# digital_led_panel.net
KiCad netlist of a schematic drawn in Altium Designer
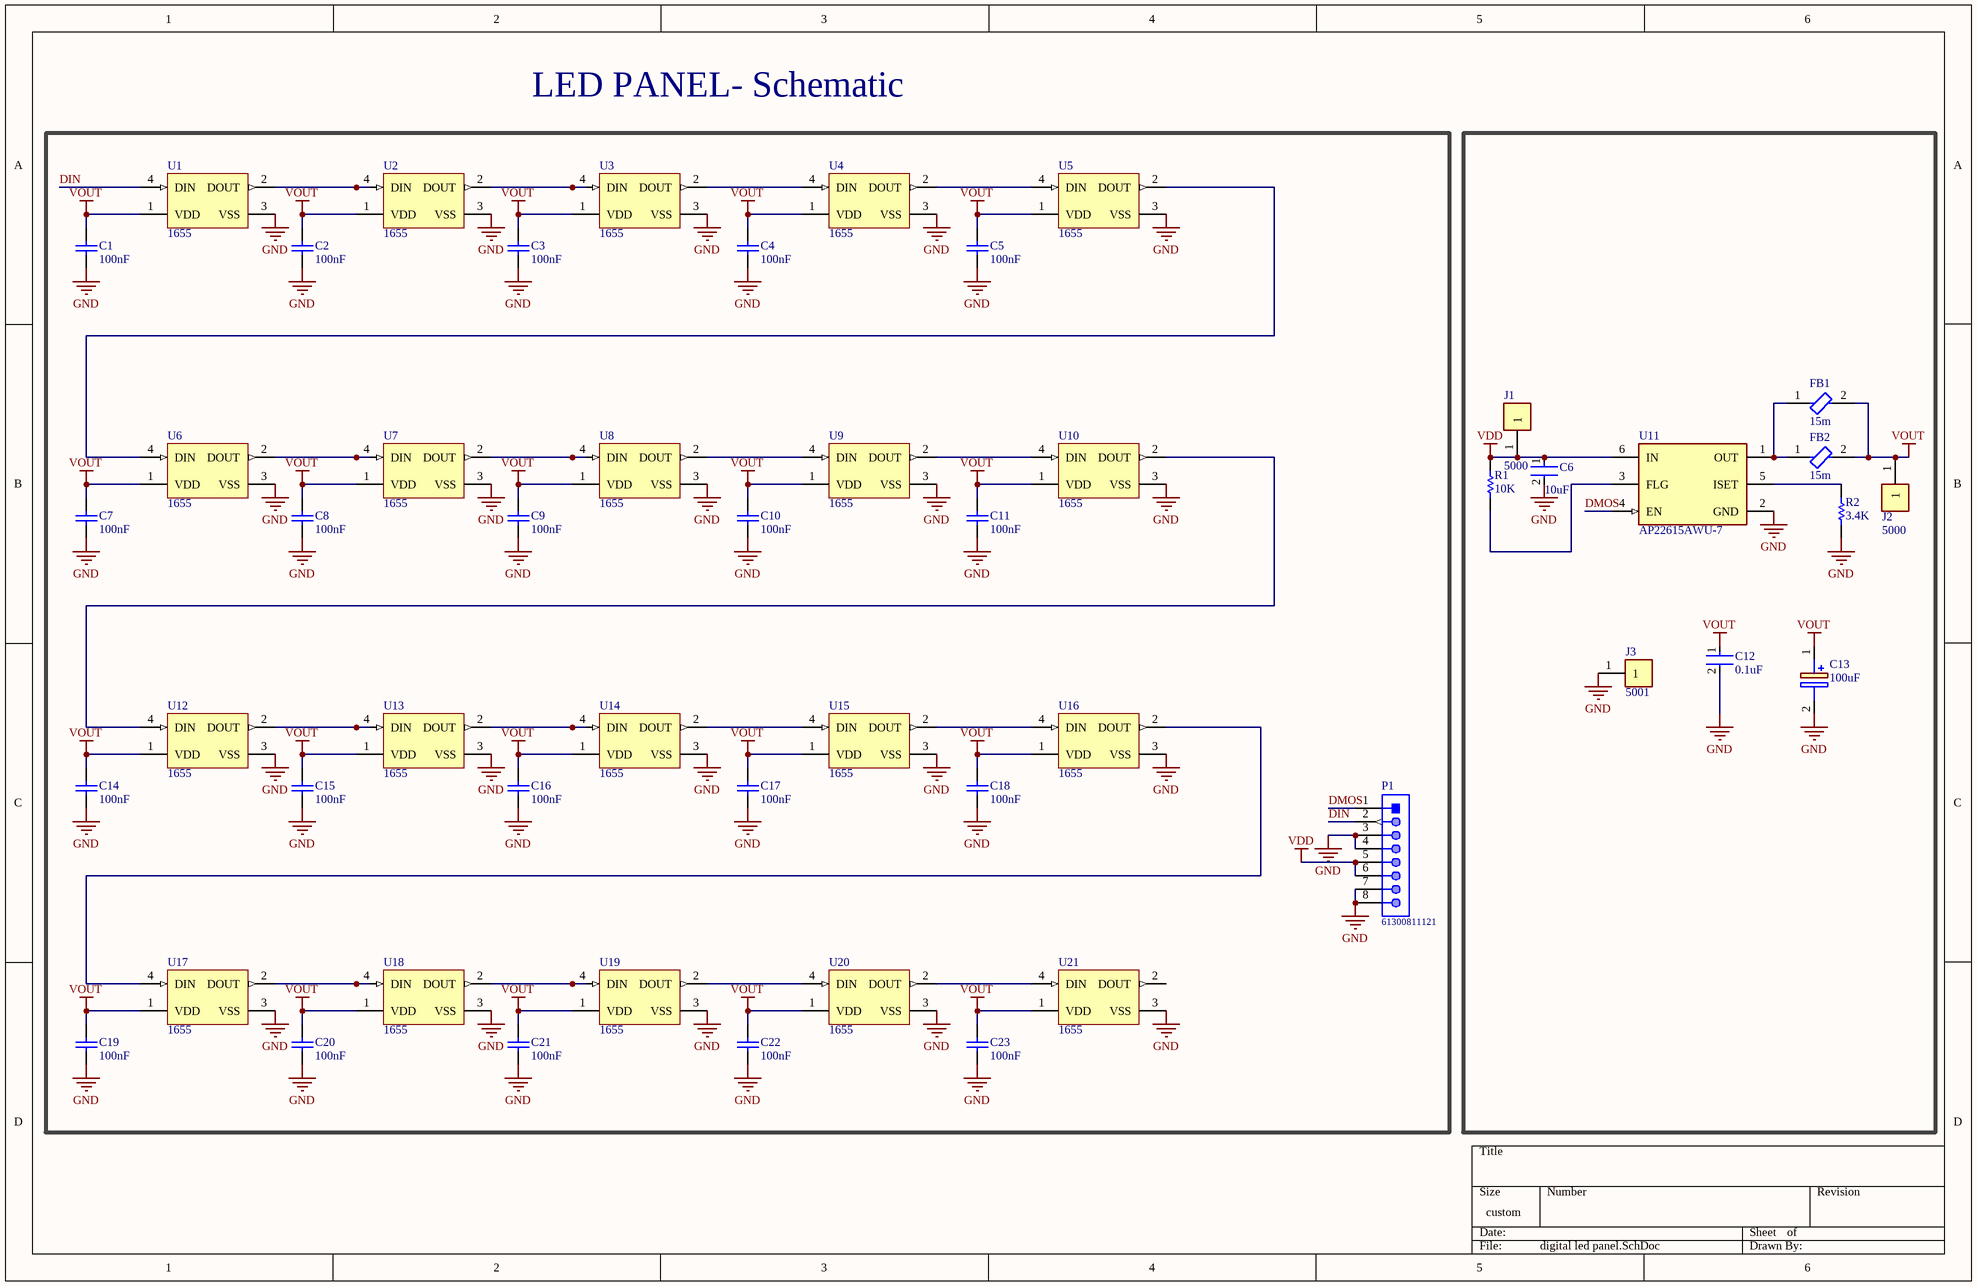
[diagram p0: digital led panel.SchDoc]

(export (version "E")
  (design (tool "Eeschema 10.0.6"))
  (components
    (comp (ref "C1")
      (value "100nF")
      (footprint "KEMT-1206-2_M")
      (description "CAP, Ceramic, 0.1 uF, +/- 10%, 50 V, -55 to 125 degC, 1206 (3216 Metric), RoHS, Tape and Reel")
      (fields (field (name "MANUFACTURER") "Kemet"))
      (libsource (lib "Altium Content Vault") (part "CAP-NP-2"))
    )
    (comp (ref "C2")
      (value "100nF")
      (footprint "KEMT-1206-2_M")
      (description "CAP, Ceramic, 0.1 uF, +/- 10%, 50 V, -55 to 125 degC, 1206 (3216 Metric), RoHS, Tape and Reel")
      (fields (field (name "MANUFACTURER") "Kemet"))
      (libsource (lib "Altium Content Vault") (part "CAP-NP-2"))
    )
    (comp (ref "C3")
      (value "100nF")
      (footprint "KEMT-1206-2_M")
      (description "CAP, Ceramic, 0.1 uF, +/- 10%, 50 V, -55 to 125 degC, 1206 (3216 Metric), RoHS, Tape and Reel")
      (fields (field (name "MANUFACTURER") "Kemet"))
      (libsource (lib "Altium Content Vault") (part "CAP-NP-2"))
    )
    (comp (ref "C4")
      (value "100nF")
      (footprint "KEMT-1206-2_M")
      (description "CAP, Ceramic, 0.1 uF, +/- 10%, 50 V, -55 to 125 degC, 1206 (3216 Metric), RoHS, Tape and Reel")
      (fields (field (name "MANUFACTURER") "Kemet"))
      (libsource (lib "Altium Content Vault") (part "CAP-NP-2"))
    )
    (comp (ref "C5")
      (value "100nF")
      (footprint "KEMT-1206-2_M")
      (description "CAP, Ceramic, 0.1 uF, +/- 10%, 50 V, -55 to 125 degC, 1206 (3216 Metric), RoHS, Tape and Reel")
      (fields (field (name "MANUFACTURER") "Kemet"))
      (libsource (lib "Altium Content Vault") (part "CAP-NP-2"))
    )
    (comp (ref "C6")
      (value "10uF")
      (footprint "FP-1206-L_3_2_0_2-W_1_6_0-IPC_A")
      (description "General Purpose Ceramic Capacitor, 1206, 10uF, 10%, X5R, 15%, 10V")
      (fields (field (name "TOLERANCE") "10%") (field (name "VOLTAGE") "10V"))
      (libsource (lib "Altium Content Vault") (part "02cd4be3c70576c341d710602a673aa"))
    )
    (comp (ref "C7")
      (value "100nF")
      (footprint "KEMT-1206-2_M")
      (description "CAP, Ceramic, 0.1 uF, +/- 10%, 50 V, -55 to 125 degC, 1206 (3216 Metric), RoHS, Tape and Reel")
      (fields (field (name "MANUFACTURER") "Kemet"))
      (libsource (lib "Altium Content Vault") (part "CAP-NP-2"))
    )
    (comp (ref "C8")
      (value "100nF")
      (footprint "KEMT-1206-2_M")
      (description "CAP, Ceramic, 0.1 uF, +/- 10%, 50 V, -55 to 125 degC, 1206 (3216 Metric), RoHS, Tape and Reel")
      (fields (field (name "MANUFACTURER") "Kemet"))
      (libsource (lib "Altium Content Vault") (part "CAP-NP-2"))
    )
    (comp (ref "C9")
      (value "100nF")
      (footprint "KEMT-1206-2_M")
      (description "CAP, Ceramic, 0.1 uF, +/- 10%, 50 V, -55 to 125 degC, 1206 (3216 Metric), RoHS, Tape and Reel")
      (fields (field (name "MANUFACTURER") "Kemet"))
      (libsource (lib "Altium Content Vault") (part "CAP-NP-2"))
    )
    (comp (ref "C10")
      (value "100nF")
      (footprint "KEMT-1206-2_M")
      (description "CAP, Ceramic, 0.1 uF, +/- 10%, 50 V, -55 to 125 degC, 1206 (3216 Metric), RoHS, Tape and Reel")
      (fields (field (name "MANUFACTURER") "Kemet"))
      (libsource (lib "Altium Content Vault") (part "CAP-NP-2"))
    )
    (comp (ref "C11")
      (value "100nF")
      (footprint "KEMT-1206-2_M")
      (description "CAP, Ceramic, 0.1 uF, +/- 10%, 50 V, -55 to 125 degC, 1206 (3216 Metric), RoHS, Tape and Reel")
      (fields (field (name "MANUFACTURER") "Kemet"))
      (libsource (lib "Altium Content Vault") (part "CAP-NP-2"))
    )
    (comp (ref "C12")
      (value "0.1uF")
      (footprint "FP-C1206C-EB-MFG")
      (description "CAP CER 0.1UF 100V X7R 1206")
      (fields
        (field (name "TOLERANCE") "0.1")
        (field (name "OCTOPART") "https://octopart.com/c1206c104k1ractu-kemet-89521")
      )
      (libsource (lib "Altium Content Vault") (part "b4654b650e69147ec39a6b967a45e02"))
    )
    (comp (ref "C13")
      (value "100uF")
      (footprint "SamacSys:CAPAE660X565N")
      (description "Capacitor Polarised")
      (fields
        (field (name "MANUFACTURER_PART_NUMBER") "EEV107M016S9GAA")
        (field (name "MOUSER PART NUMBER") "80-EEV107M016S9GAA")
      )
      (libsource (lib "*") (part "EEV107M016S9GAA"))
    )
    (comp (ref "C14")
      (value "100nF")
      (footprint "KEMT-1206-2_M")
      (description "CAP, Ceramic, 0.1 uF, +/- 10%, 50 V, -55 to 125 degC, 1206 (3216 Metric), RoHS, Tape and Reel")
      (fields (field (name "MANUFACTURER") "Kemet"))
      (libsource (lib "Altium Content Vault") (part "CAP-NP-2"))
    )
    (comp (ref "C15")
      (value "100nF")
      (footprint "KEMT-1206-2_M")
      (description "CAP, Ceramic, 0.1 uF, +/- 10%, 50 V, -55 to 125 degC, 1206 (3216 Metric), RoHS, Tape and Reel")
      (fields (field (name "MANUFACTURER") "Kemet"))
      (libsource (lib "Altium Content Vault") (part "CAP-NP-2"))
    )
    (comp (ref "C16")
      (value "100nF")
      (footprint "KEMT-1206-2_M")
      (description "CAP, Ceramic, 0.1 uF, +/- 10%, 50 V, -55 to 125 degC, 1206 (3216 Metric), RoHS, Tape and Reel")
      (fields (field (name "MANUFACTURER") "Kemet"))
      (libsource (lib "Altium Content Vault") (part "CAP-NP-2"))
    )
    (comp (ref "C17")
      (value "100nF")
      (footprint "KEMT-1206-2_M")
      (description "CAP, Ceramic, 0.1 uF, +/- 10%, 50 V, -55 to 125 degC, 1206 (3216 Metric), RoHS, Tape and Reel")
      (fields (field (name "MANUFACTURER") "Kemet"))
      (libsource (lib "Altium Content Vault") (part "CAP-NP-2"))
    )
    (comp (ref "C18")
      (value "100nF")
      (footprint "KEMT-1206-2_M")
      (description "CAP, Ceramic, 0.1 uF, +/- 10%, 50 V, -55 to 125 degC, 1206 (3216 Metric), RoHS, Tape and Reel")
      (fields (field (name "MANUFACTURER") "Kemet"))
      (libsource (lib "Altium Content Vault") (part "CAP-NP-2"))
    )
    (comp (ref "C19")
      (value "100nF")
      (footprint "KEMT-1206-2_M")
      (description "CAP, Ceramic, 0.1 uF, +/- 10%, 50 V, -55 to 125 degC, 1206 (3216 Metric), RoHS, Tape and Reel")
      (fields (field (name "MANUFACTURER") "Kemet"))
      (libsource (lib "Altium Content Vault") (part "CAP-NP-2"))
    )
    (comp (ref "C20")
      (value "100nF")
      (footprint "KEMT-1206-2_M")
      (description "CAP, Ceramic, 0.1 uF, +/- 10%, 50 V, -55 to 125 degC, 1206 (3216 Metric), RoHS, Tape and Reel")
      (fields (field (name "MANUFACTURER") "Kemet"))
      (libsource (lib "Altium Content Vault") (part "CAP-NP-2"))
    )
    (comp (ref "C21")
      (value "100nF")
      (footprint "KEMT-1206-2_M")
      (description "CAP, Ceramic, 0.1 uF, +/- 10%, 50 V, -55 to 125 degC, 1206 (3216 Metric), RoHS, Tape and Reel")
      (fields (field (name "MANUFACTURER") "Kemet"))
      (libsource (lib "Altium Content Vault") (part "CAP-NP-2"))
    )
    (comp (ref "C22")
      (value "100nF")
      (footprint "KEMT-1206-2_M")
      (description "CAP, Ceramic, 0.1 uF, +/- 10%, 50 V, -55 to 125 degC, 1206 (3216 Metric), RoHS, Tape and Reel")
      (fields (field (name "MANUFACTURER") "Kemet"))
      (libsource (lib "Altium Content Vault") (part "CAP-NP-2"))
    )
    (comp (ref "C23")
      (value "100nF")
      (footprint "KEMT-1206-2_M")
      (description "CAP, Ceramic, 0.1 uF, +/- 10%, 50 V, -55 to 125 degC, 1206 (3216 Metric), RoHS, Tape and Reel")
      (fields (field (name "MANUFACTURER") "Kemet"))
      (libsource (lib "Altium Content Vault") (part "CAP-NP-2"))
    )
    (comp (ref "FB1")
      (value "15m")
      (footprint "FP-BLM21-0_2-t0_85-e0_5-d-IPC_B")
      (description "Chip Ferrite Bead, 0805, 30Ω @ 100MHz, 0.014Ω, , 4A")
      (fields (field (name "TOLERANCE") "25%"))
      (libsource (lib "Altium Content Vault") (part "5f30dd21d616792df468990f7003faa"))
    )
    (comp (ref "FB2")
      (value "15m")
      (footprint "FP-BLM21-0_2-t0_85-e0_5-d-IPC_B")
      (description "Chip Ferrite Bead, 0805, 30Ω @ 100MHz, 0.014Ω, , 4A")
      (fields (field (name "TOLERANCE") "25%"))
      (libsource (lib "Altium Content Vault") (part "5f30dd21d616792df468990f7003faa"))
    )
    (comp (ref "J1")
      (value "5000")
      (footprint "FP-5000-MFG")
      (description "PC TEST POINT MINIATURE RED")
      (libsource (lib "Altium Content Vault") (part "1e4615820a309e3ce90f9e6d957b7fa"))
    )
    (comp (ref "J2")
      (value "5000")
      (footprint "FP-5000-MFG")
      (description "PC TEST POINT MINIATURE RED")
      (libsource (lib "") (part "1e4615820a309e3ce90f9e6d957b7fa_2"))
    )
    (comp (ref "J3")
      (value "5001")
      (footprint "FP-5001-MFG")
      (description "PC TEST POINT MINIATURE BLACK")
      (libsource (lib "") (part "1e4615820a309e3ce90f9e6d957b7fa_1"))
    )
    (comp (ref "P1")
      (value "61300811121")
      (footprint "61300811121")
      (description "THT Vertical Pin Header WR-PHD, Pitch 2.54 mm, Single Row, 8 pins")
      (fields (field (name "MANUFACTURER") "Wurth Elektronik") (field (name "PUBLISHER") "WurthElektronik"))
      (libsource (lib "Altium Content Vault") (part "WE-CN-1P-M-R8"))
    )
    (comp (ref "R1")
      (value "10K")
      (footprint "RESC3116X65X40ML10T20")
      (description "Chip Resistor, 10 KOhm, +/- 1%, 0.25 W, -55 to 155 degC, 1206 (3216 Metric), RoHS, Tape and Reel")
      (fields (field (name "TOLERANCE") "1%") (field (name "MANUFACTURER") "Yageo"))
      (libsource (lib "Altium Content Vault") (part "RES-2"))
    )
    (comp (ref "R2")
      (value "3.4K")
      (footprint "RESC3216X70X50LL05T20")
      (fields (field (name "PART NUMBER") "ERJ-8ENF3401V") (field (name "MANUFACTURER") "Panasonic"))
      (libsource (lib "Altium Content Vault") (part "RES"))
    )
    (comp (ref "U1")
      (value "1655")
      (footprint "ADA-RGB-1655_V")
      (fields (field (name "MANUFACTURER") "Adafruit-Industries-LLC"))
      (libsource (lib "Altium Content Vault") (part "ADA-RGB-1655-4"))
    )
    (comp (ref "U2")
      (value "1655")
      (footprint "ADA-RGB-1655_V")
      (fields (field (name "MANUFACTURER") "Adafruit-Industries-LLC"))
      (libsource (lib "Altium Content Vault") (part "ADA-RGB-1655-4"))
    )
    (comp (ref "U3")
      (value "1655")
      (footprint "ADA-RGB-1655_V")
      (fields (field (name "MANUFACTURER") "Adafruit-Industries-LLC"))
      (libsource (lib "Altium Content Vault") (part "ADA-RGB-1655-4"))
    )
    (comp (ref "U4")
      (value "1655")
      (footprint "ADA-RGB-1655_V")
      (fields (field (name "MANUFACTURER") "Adafruit-Industries-LLC"))
      (libsource (lib "Altium Content Vault") (part "ADA-RGB-1655-4"))
    )
    (comp (ref "U5")
      (value "1655")
      (footprint "ADA-RGB-1655_V")
      (fields (field (name "MANUFACTURER") "Adafruit-Industries-LLC"))
      (libsource (lib "Altium Content Vault") (part "ADA-RGB-1655-4"))
    )
    (comp (ref "U6")
      (value "1655")
      (footprint "ADA-RGB-1655_V")
      (fields (field (name "MANUFACTURER") "Adafruit-Industries-LLC"))
      (libsource (lib "Altium Content Vault") (part "ADA-RGB-1655-4"))
    )
    (comp (ref "U7")
      (value "1655")
      (footprint "ADA-RGB-1655_V")
      (fields (field (name "MANUFACTURER") "Adafruit-Industries-LLC"))
      (libsource (lib "Altium Content Vault") (part "ADA-RGB-1655-4"))
    )
    (comp (ref "U8")
      (value "1655")
      (footprint "ADA-RGB-1655_V")
      (fields (field (name "MANUFACTURER") "Adafruit-Industries-LLC"))
      (libsource (lib "Altium Content Vault") (part "ADA-RGB-1655-4"))
    )
    (comp (ref "U9")
      (value "1655")
      (footprint "ADA-RGB-1655_V")
      (fields (field (name "MANUFACTURER") "Adafruit-Industries-LLC"))
      (libsource (lib "Altium Content Vault") (part "ADA-RGB-1655-4"))
    )
    (comp (ref "U10")
      (value "1655")
      (footprint "ADA-RGB-1655_V")
      (fields (field (name "MANUFACTURER") "Adafruit-Industries-LLC"))
      (libsource (lib "Altium Content Vault") (part "ADA-RGB-1655-4"))
    )
    (comp (ref "U11")
      (value "AP22615AWU-7")
      (footprint "FP-TSOT26-IPC_B")
      (description "IC PWR SWTCH N/P-CHAN 1:1 TSOT26")
      (libsource (lib "Altium Content Vault") (part "63b513322e128d9fcafbe9b26c13419"))
    )
    (comp (ref "U12")
      (value "1655")
      (footprint "ADA-RGB-1655_V")
      (fields (field (name "MANUFACTURER") "Adafruit-Industries-LLC"))
      (libsource (lib "Altium Content Vault") (part "ADA-RGB-1655-4"))
    )
    (comp (ref "U13")
      (value "1655")
      (footprint "ADA-RGB-1655_V")
      (fields (field (name "MANUFACTURER") "Adafruit-Industries-LLC"))
      (libsource (lib "Altium Content Vault") (part "ADA-RGB-1655-4"))
    )
    (comp (ref "U14")
      (value "1655")
      (footprint "ADA-RGB-1655_V")
      (fields (field (name "MANUFACTURER") "Adafruit-Industries-LLC"))
      (libsource (lib "Altium Content Vault") (part "ADA-RGB-1655-4"))
    )
    (comp (ref "U15")
      (value "1655")
      (footprint "ADA-RGB-1655_V")
      (fields (field (name "MANUFACTURER") "Adafruit-Industries-LLC"))
      (libsource (lib "Altium Content Vault") (part "ADA-RGB-1655-4"))
    )
    (comp (ref "U16")
      (value "1655")
      (footprint "ADA-RGB-1655_V")
      (fields (field (name "MANUFACTURER") "Adafruit-Industries-LLC"))
      (libsource (lib "Altium Content Vault") (part "ADA-RGB-1655-4"))
    )
    (comp (ref "U17")
      (value "1655")
      (footprint "ADA-RGB-1655_V")
      (fields (field (name "MANUFACTURER") "Adafruit-Industries-LLC"))
      (libsource (lib "Altium Content Vault") (part "ADA-RGB-1655-4"))
    )
    (comp (ref "U18")
      (value "1655")
      (footprint "ADA-RGB-1655_V")
      (fields (field (name "MANUFACTURER") "Adafruit-Industries-LLC"))
      (libsource (lib "Altium Content Vault") (part "ADA-RGB-1655-4"))
    )
    (comp (ref "U19")
      (value "1655")
      (footprint "ADA-RGB-1655_V")
      (fields (field (name "MANUFACTURER") "Adafruit-Industries-LLC"))
      (libsource (lib "Altium Content Vault") (part "ADA-RGB-1655-4"))
    )
    (comp (ref "U20")
      (value "1655")
      (footprint "ADA-RGB-1655_V")
      (fields (field (name "MANUFACTURER") "Adafruit-Industries-LLC"))
      (libsource (lib "Altium Content Vault") (part "ADA-RGB-1655-4"))
    )
    (comp (ref "U21")
      (value "1655")
      (footprint "ADA-RGB-1655_V")
      (fields (field (name "MANUFACTURER") "Adafruit-Industries-LLC"))
      (libsource (lib "Altium Content Vault") (part "ADA-RGB-1655-4"))
    )
  )
  (nets
    (net (code "1") (name "/DIN") (class "Default")
      (node (ref "P1") (pin "2") (pinfunction "2_2") (pintype "output"))
      (node (ref "U1") (pin "4") (pinfunction "DIN_4") (pintype "input"))
    )
    (net (code "2") (name "/DMOS") (class "Default")
      (node (ref "P1") (pin "1") (pinfunction "1_1") (pintype "passive"))
      (node (ref "U11") (pin "4") (pinfunction "EN_4") (pintype "input"))
    )
    (net (code "3") (name "GND") (class "Default")
      (node (ref "C1") (pin "1") (pinfunction "1_1") (pintype "passive"))
      (node (ref "C10") (pin "1") (pinfunction "1_1") (pintype "passive"))
      (node (ref "C11") (pin "1") (pinfunction "1_1") (pintype "passive"))
      (node (ref "C12") (pin "2") (pinfunction "2_2") (pintype "passive"))
      (node (ref "C13") (pin "2") (pinfunction "-_2") (pintype "passive"))
      (node (ref "C14") (pin "1") (pinfunction "1_1") (pintype "passive"))
      (node (ref "C15") (pin "1") (pinfunction "1_1") (pintype "passive"))
      (node (ref "C16") (pin "1") (pinfunction "1_1") (pintype "passive"))
      (node (ref "C17") (pin "1") (pinfunction "1_1") (pintype "passive"))
      (node (ref "C18") (pin "1") (pinfunction "1_1") (pintype "passive"))
      (node (ref "C19") (pin "1") (pinfunction "1_1") (pintype "passive"))
      (node (ref "C2") (pin "1") (pinfunction "1_1") (pintype "passive"))
      (node (ref "C20") (pin "1") (pinfunction "1_1") (pintype "passive"))
      (node (ref "C21") (pin "1") (pinfunction "1_1") (pintype "passive"))
      (node (ref "C22") (pin "1") (pinfunction "1_1") (pintype "passive"))
      (node (ref "C23") (pin "1") (pinfunction "1_1") (pintype "passive"))
      (node (ref "C3") (pin "1") (pinfunction "1_1") (pintype "passive"))
      (node (ref "C4") (pin "1") (pinfunction "1_1") (pintype "passive"))
      (node (ref "C5") (pin "1") (pinfunction "1_1") (pintype "passive"))
      (node (ref "C6") (pin "2") (pinfunction "2_2") (pintype "passive"))
      (node (ref "C7") (pin "1") (pinfunction "1_1") (pintype "passive"))
      (node (ref "C8") (pin "1") (pinfunction "1_1") (pintype "passive"))
      (node (ref "C9") (pin "1") (pinfunction "1_1") (pintype "passive"))
      (node (ref "J3") (pin "1") (pinfunction "1_1") (pintype "passive"))
      (node (ref "P1") (pin "3") (pinfunction "3_3") (pintype "passive"))
      (node (ref "P1") (pin "4") (pinfunction "4_4") (pintype "passive"))
      (node (ref "P1") (pin "7") (pinfunction "7_7") (pintype "passive"))
      (node (ref "P1") (pin "8") (pinfunction "8_8") (pintype "passive"))
      (node (ref "R2") (pin "1") (pinfunction "1_1") (pintype "passive"))
      (node (ref "U1") (pin "3") (pinfunction "VSS_3") (pintype "power_in"))
      (node (ref "U10") (pin "3") (pinfunction "VSS_3") (pintype "power_in"))
      (node (ref "U11") (pin "2") (pinfunction "GND_2") (pintype "power_in"))
      (node (ref "U12") (pin "3") (pinfunction "VSS_3") (pintype "power_in"))
      (node (ref "U13") (pin "3") (pinfunction "VSS_3") (pintype "power_in"))
      (node (ref "U14") (pin "3") (pinfunction "VSS_3") (pintype "power_in"))
      (node (ref "U15") (pin "3") (pinfunction "VSS_3") (pintype "power_in"))
      (node (ref "U16") (pin "3") (pinfunction "VSS_3") (pintype "power_in"))
      (node (ref "U17") (pin "3") (pinfunction "VSS_3") (pintype "power_in"))
      (node (ref "U18") (pin "3") (pinfunction "VSS_3") (pintype "power_in"))
      (node (ref "U19") (pin "3") (pinfunction "VSS_3") (pintype "power_in"))
      (node (ref "U2") (pin "3") (pinfunction "VSS_3") (pintype "power_in"))
      (node (ref "U20") (pin "3") (pinfunction "VSS_3") (pintype "power_in"))
      (node (ref "U21") (pin "3") (pinfunction "VSS_3") (pintype "power_in"))
      (node (ref "U3") (pin "3") (pinfunction "VSS_3") (pintype "power_in"))
      (node (ref "U4") (pin "3") (pinfunction "VSS_3") (pintype "power_in"))
      (node (ref "U5") (pin "3") (pinfunction "VSS_3") (pintype "power_in"))
      (node (ref "U6") (pin "3") (pinfunction "VSS_3") (pintype "power_in"))
      (node (ref "U7") (pin "3") (pinfunction "VSS_3") (pintype "power_in"))
      (node (ref "U8") (pin "3") (pinfunction "VSS_3") (pintype "power_in"))
      (node (ref "U9") (pin "3") (pinfunction "VSS_3") (pintype "power_in"))
    )
    (net (code "4") (name "Net-(U1-DOUT)") (class "Default")
      (node (ref "U1") (pin "2") (pinfunction "DOUT_2") (pintype "output"))
      (node (ref "U2") (pin "4") (pinfunction "DIN_4") (pintype "input"))
    )
    (net (code "5") (name "Net-(U2-DOUT)") (class "Default")
      (node (ref "U2") (pin "2") (pinfunction "DOUT_2") (pintype "output"))
      (node (ref "U3") (pin "4") (pinfunction "DIN_4") (pintype "input"))
    )
    (net (code "6") (name "Net-(U3-DOUT)") (class "Default")
      (node (ref "U3") (pin "2") (pinfunction "DOUT_2") (pintype "output"))
      (node (ref "U4") (pin "4") (pinfunction "DIN_4") (pintype "input"))
    )
    (net (code "7") (name "Net-(U4-DOUT)") (class "Default")
      (node (ref "U4") (pin "2") (pinfunction "DOUT_2") (pintype "output"))
      (node (ref "U5") (pin "4") (pinfunction "DIN_4") (pintype "input"))
    )
    (net (code "8") (name "Net-(U5-DOUT)") (class "Default")
      (node (ref "U5") (pin "2") (pinfunction "DOUT_2") (pintype "output"))
      (node (ref "U6") (pin "4") (pinfunction "DIN_4") (pintype "input"))
    )
    (net (code "9") (name "Net-(U6-DOUT)") (class "Default")
      (node (ref "U6") (pin "2") (pinfunction "DOUT_2") (pintype "output"))
      (node (ref "U7") (pin "4") (pinfunction "DIN_4") (pintype "input"))
    )
    (net (code "10") (name "Net-(U7-DOUT)") (class "Default")
      (node (ref "U7") (pin "2") (pinfunction "DOUT_2") (pintype "output"))
      (node (ref "U8") (pin "4") (pinfunction "DIN_4") (pintype "input"))
    )
    (net (code "11") (name "Net-(U8-DOUT)") (class "Default")
      (node (ref "U8") (pin "2") (pinfunction "DOUT_2") (pintype "output"))
      (node (ref "U9") (pin "4") (pinfunction "DIN_4") (pintype "input"))
    )
    (net (code "12") (name "Net-(U10-DIN)") (class "Default")
      (node (ref "U10") (pin "4") (pinfunction "DIN_4") (pintype "input"))
      (node (ref "U9") (pin "2") (pinfunction "DOUT_2") (pintype "output"))
    )
    (net (code "13") (name "Net-(U10-DOUT)") (class "Default")
      (node (ref "U10") (pin "2") (pinfunction "DOUT_2") (pintype "output"))
      (node (ref "U12") (pin "4") (pinfunction "DIN_4") (pintype "input"))
    )
    (net (code "14") (name "Net-(U11-FLG)") (class "Default")
      (node (ref "R1") (pin "1") (pinfunction "1_1") (pintype "passive"))
      (node (ref "U11") (pin "3") (pinfunction "FLG_3") (pintype "passive"))
    )
    (net (code "15") (name "Net-(U11-ISET)") (class "Default")
      (node (ref "R2") (pin "2") (pinfunction "2_2") (pintype "passive"))
      (node (ref "U11") (pin "5") (pinfunction "ISET_5") (pintype "passive"))
    )
    (net (code "16") (name "Net-(U11-OUT)") (class "Default")
      (node (ref "FB1") (pin "1") (pinfunction "1_1") (pintype "passive"))
      (node (ref "FB2") (pin "1") (pinfunction "1_1") (pintype "passive"))
      (node (ref "U11") (pin "1") (pinfunction "OUT_1") (pintype "power_in"))
    )
    (net (code "17") (name "Net-(U12-DOUT)") (class "Default")
      (node (ref "U12") (pin "2") (pinfunction "DOUT_2") (pintype "output"))
      (node (ref "U13") (pin "4") (pinfunction "DIN_4") (pintype "input"))
    )
    (net (code "18") (name "Net-(U13-DOUT)") (class "Default")
      (node (ref "U13") (pin "2") (pinfunction "DOUT_2") (pintype "output"))
      (node (ref "U14") (pin "4") (pinfunction "DIN_4") (pintype "input"))
    )
    (net (code "19") (name "Net-(U14-DOUT)") (class "Default")
      (node (ref "U14") (pin "2") (pinfunction "DOUT_2") (pintype "output"))
      (node (ref "U15") (pin "4") (pinfunction "DIN_4") (pintype "input"))
    )
    (net (code "20") (name "Net-(U15-DOUT)") (class "Default")
      (node (ref "U15") (pin "2") (pinfunction "DOUT_2") (pintype "output"))
      (node (ref "U16") (pin "4") (pinfunction "DIN_4") (pintype "input"))
    )
    (net (code "21") (name "Net-(U16-DOUT)") (class "Default")
      (node (ref "U16") (pin "2") (pinfunction "DOUT_2") (pintype "output"))
      (node (ref "U17") (pin "4") (pinfunction "DIN_4") (pintype "input"))
    )
    (net (code "22") (name "Net-(U17-DOUT)") (class "Default")
      (node (ref "U17") (pin "2") (pinfunction "DOUT_2") (pintype "output"))
      (node (ref "U18") (pin "4") (pinfunction "DIN_4") (pintype "input"))
    )
    (net (code "23") (name "Net-(U18-DOUT)") (class "Default")
      (node (ref "U18") (pin "2") (pinfunction "DOUT_2") (pintype "output"))
      (node (ref "U19") (pin "4") (pinfunction "DIN_4") (pintype "input"))
    )
    (net (code "24") (name "Net-(U19-DOUT)") (class "Default")
      (node (ref "U19") (pin "2") (pinfunction "DOUT_2") (pintype "output"))
      (node (ref "U20") (pin "4") (pinfunction "DIN_4") (pintype "input"))
    )
    (net (code "25") (name "Net-(U20-DOUT)") (class "Default")
      (node (ref "U20") (pin "2") (pinfunction "DOUT_2") (pintype "output"))
      (node (ref "U21") (pin "4") (pinfunction "DIN_4") (pintype "input"))
    )
    (net (code "26") (name "VDD") (class "Default")
      (node (ref "C6") (pin "1") (pinfunction "1_1") (pintype "passive"))
      (node (ref "J1") (pin "1") (pinfunction "1_1") (pintype "passive"))
      (node (ref "P1") (pin "5") (pinfunction "5_5") (pintype "passive"))
      (node (ref "P1") (pin "6") (pinfunction "6_6") (pintype "passive"))
      (node (ref "R1") (pin "2") (pinfunction "2_2") (pintype "passive"))
      (node (ref "U11") (pin "6") (pinfunction "IN_6") (pintype "power_in"))
    )
    (net (code "27") (name "VOUT") (class "Default")
      (node (ref "C1") (pin "2") (pinfunction "2_2") (pintype "passive"))
      (node (ref "C10") (pin "2") (pinfunction "2_2") (pintype "passive"))
      (node (ref "C11") (pin "2") (pinfunction "2_2") (pintype "passive"))
      (node (ref "C12") (pin "1") (pinfunction "1_1") (pintype "passive"))
      (node (ref "C13") (pin "1") (pinfunction "+_1") (pintype "passive"))
      (node (ref "C14") (pin "2") (pinfunction "2_2") (pintype "passive"))
      (node (ref "C15") (pin "2") (pinfunction "2_2") (pintype "passive"))
      (node (ref "C16") (pin "2") (pinfunction "2_2") (pintype "passive"))
      (node (ref "C17") (pin "2") (pinfunction "2_2") (pintype "passive"))
      (node (ref "C18") (pin "2") (pinfunction "2_2") (pintype "passive"))
      (node (ref "C19") (pin "2") (pinfunction "2_2") (pintype "passive"))
      (node (ref "C2") (pin "2") (pinfunction "2_2") (pintype "passive"))
      (node (ref "C20") (pin "2") (pinfunction "2_2") (pintype "passive"))
      (node (ref "C21") (pin "2") (pinfunction "2_2") (pintype "passive"))
      (node (ref "C22") (pin "2") (pinfunction "2_2") (pintype "passive"))
      (node (ref "C23") (pin "2") (pinfunction "2_2") (pintype "passive"))
      (node (ref "C3") (pin "2") (pinfunction "2_2") (pintype "passive"))
      (node (ref "C4") (pin "2") (pinfunction "2_2") (pintype "passive"))
      (node (ref "C5") (pin "2") (pinfunction "2_2") (pintype "passive"))
      (node (ref "C7") (pin "2") (pinfunction "2_2") (pintype "passive"))
      (node (ref "C8") (pin "2") (pinfunction "2_2") (pintype "passive"))
      (node (ref "C9") (pin "2") (pinfunction "2_2") (pintype "passive"))
      (node (ref "FB1") (pin "2") (pinfunction "2_2") (pintype "passive"))
      (node (ref "FB2") (pin "2") (pinfunction "2_2") (pintype "passive"))
      (node (ref "J2") (pin "1") (pinfunction "1_1") (pintype "passive"))
      (node (ref "U1") (pin "1") (pinfunction "VDD_1") (pintype "power_in"))
      (node (ref "U10") (pin "1") (pinfunction "VDD_1") (pintype "power_in"))
      (node (ref "U12") (pin "1") (pinfunction "VDD_1") (pintype "power_in"))
      (node (ref "U13") (pin "1") (pinfunction "VDD_1") (pintype "power_in"))
      (node (ref "U14") (pin "1") (pinfunction "VDD_1") (pintype "power_in"))
      (node (ref "U15") (pin "1") (pinfunction "VDD_1") (pintype "power_in"))
      (node (ref "U16") (pin "1") (pinfunction "VDD_1") (pintype "power_in"))
      (node (ref "U17") (pin "1") (pinfunction "VDD_1") (pintype "power_in"))
      (node (ref "U18") (pin "1") (pinfunction "VDD_1") (pintype "power_in"))
      (node (ref "U19") (pin "1") (pinfunction "VDD_1") (pintype "power_in"))
      (node (ref "U2") (pin "1") (pinfunction "VDD_1") (pintype "power_in"))
      (node (ref "U20") (pin "1") (pinfunction "VDD_1") (pintype "power_in"))
      (node (ref "U21") (pin "1") (pinfunction "VDD_1") (pintype "power_in"))
      (node (ref "U3") (pin "1") (pinfunction "VDD_1") (pintype "power_in"))
      (node (ref "U4") (pin "1") (pinfunction "VDD_1") (pintype "power_in"))
      (node (ref "U5") (pin "1") (pinfunction "VDD_1") (pintype "power_in"))
      (node (ref "U6") (pin "1") (pinfunction "VDD_1") (pintype "power_in"))
      (node (ref "U7") (pin "1") (pinfunction "VDD_1") (pintype "power_in"))
      (node (ref "U8") (pin "1") (pinfunction "VDD_1") (pintype "power_in"))
      (node (ref "U9") (pin "1") (pinfunction "VDD_1") (pintype "power_in"))
    )
    (net (code "28") (name "unconnected-(U21-DOUT-Pad2)") (class "Default")
      (node (ref "U21") (pin "2") (pinfunction "DOUT_2") (pintype "output"))
    )
  )
)
